# MP-USBA.net
KiCad netlist of a schematic drawn in Altium Designer
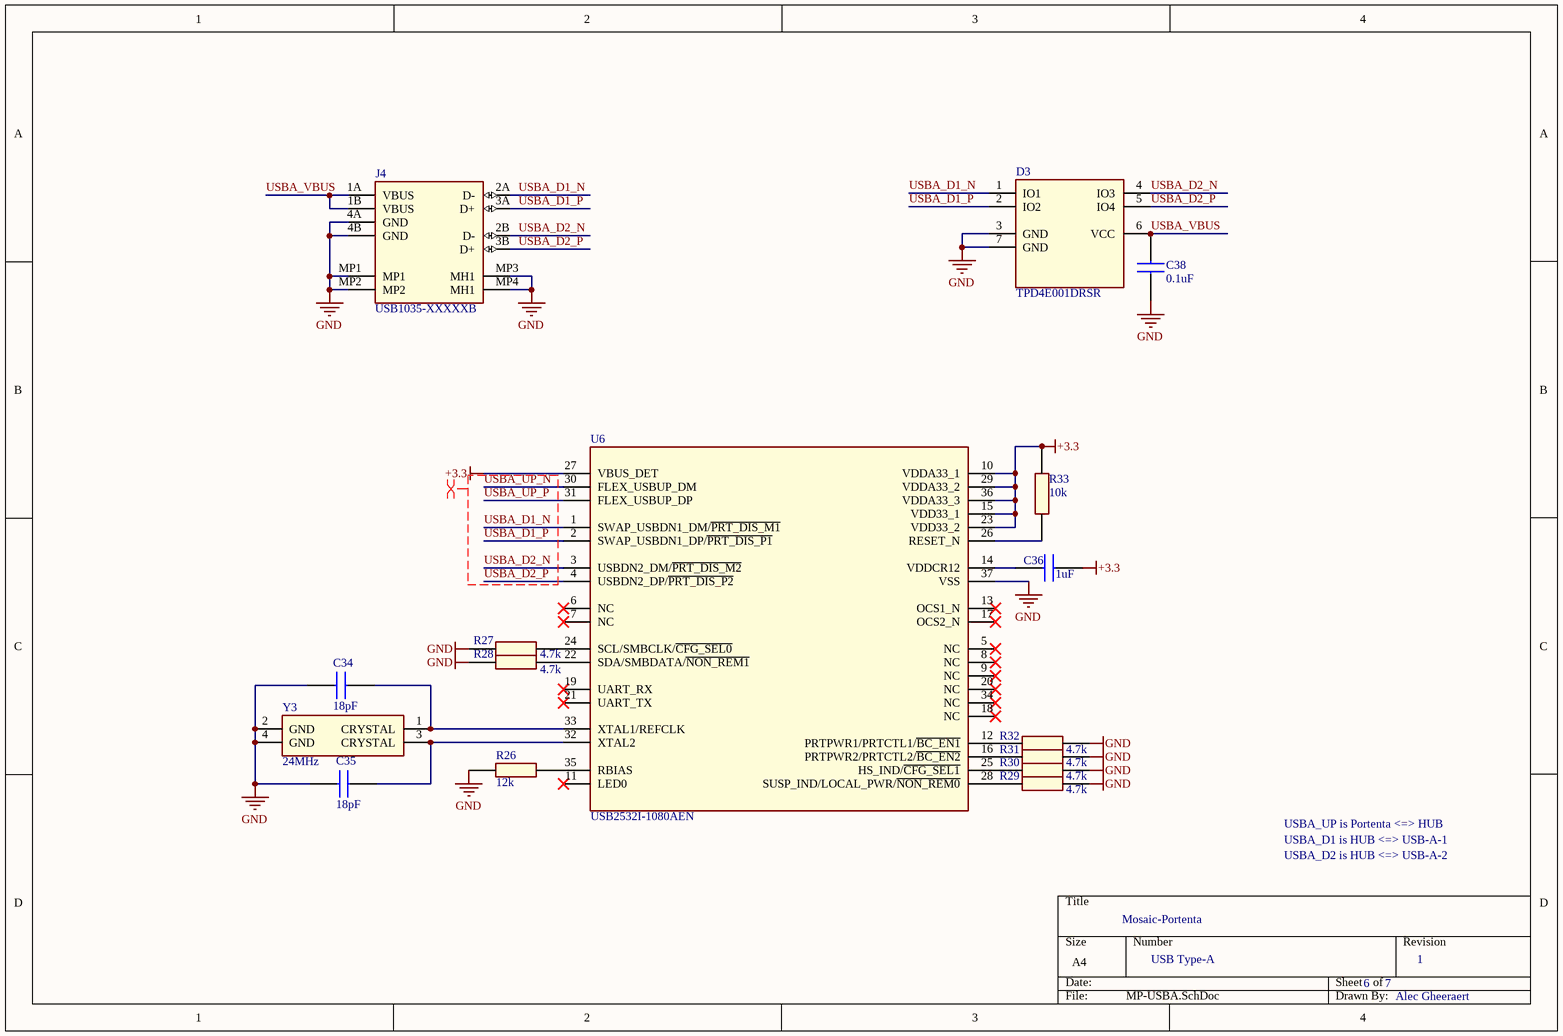
[diagram p0: MP-USBA.SchDoc]

(export (version "E")
  (design (tool "Eeschema 10.0.6"))
  (components
    (comp (ref "C34")
      (value "18pF")
      (footprint "CAPC1608X87N")
      (description "0603 18pF")
      (fields (field (name "TOLERANCE") "5%") (field (name "MANUFACTURER") "Walsin"))
      (libsource (lib "Ghrt") (part "0603N180J160CT"))
    )
    (comp (ref "C35")
      (value "18pF")
      (footprint "CAPC1608X87N")
      (description "0603 18pF")
      (fields (field (name "TOLERANCE") "5%") (field (name "MANUFACTURER") "Walsin"))
      (libsource (lib "Ghrt") (part "0603N180J160CT"))
    )
    (comp (ref "C36")
      (value "1uF")
      (footprint "CAPC1608X100N")
      (description "0603 1µF")
      (fields (field (name "MANUFACTURER") "Walsin") (field (name "TOLERANCE") "10%"))
      (libsource (lib "Ghrt") (part "0603X105K6R3CT"))
    )
    (comp (ref "C38")
      (value "0.1uF")
      (footprint "CAPC1005X55N")
      (description "0402I 0.1µF")
      (fields (field (name "MANUFACTURER") "Walsin") (field (name "TOLERANCE") "10%"))
      (libsource (lib "Ghrt") (part "MG15B104K100CT"))
    )
    (comp (ref "D3")
      (value "TPD4E001DRSR")
      (footprint "SON95P300X300X80-7N-D")
      (description "4-Channel TVS Diodes")
      (libsource (lib "Ghrt") (part "TPD4E001DRSR"))
    )
    (comp (ref "J4")
      (value "USB1035-XXXXXB")
      (footprint "USB1035-XXXXXB")
      (description "USB-2.0 Type A Dual")
      (fields (field (name "MANUFACTURER") "Global Connector Technologies"))
      (libsource (lib "Ghrt") (part "USB1035-XXXXXB"))
    )
    (comp (ref "R26")
      (value "12k")
      (footprint "RESC1005X40N")
      (description "0402I 12k")
      (fields (field (name "TOLERANCE") "1%") (field (name "MANUFACTURER") "Walsin"))
      (libsource (lib "Ghrt") (part "WR04X1202FTL"))
    )
    (comp (ref "R27")
      (value "4.7k")
      (footprint "RESC1005X40N")
      (description "0402I 4.7k")
      (fields (field (name "MANUFACTURER") "Walsin") (field (name "TOLERANCE") "1%"))
      (libsource (lib "Ghrt") (part "WR04X4701FTL"))
    )
    (comp (ref "R28")
      (value "4.7k")
      (footprint "RESC1005X40N")
      (description "0402I 4.7k")
      (fields (field (name "MANUFACTURER") "Walsin") (field (name "TOLERANCE") "1%"))
      (libsource (lib "Ghrt") (part "WR04X4701FTL"))
    )
    (comp (ref "R29")
      (value "4.7k")
      (footprint "RESC1005X40N")
      (description "0402I 4.7k")
      (fields (field (name "MANUFACTURER") "Walsin") (field (name "TOLERANCE") "1%"))
      (libsource (lib "") (part "WR04X4701FTL_1"))
    )
    (comp (ref "R30")
      (value "4.7k")
      (footprint "RESC1005X40N")
      (description "0402I 4.7k")
      (fields (field (name "MANUFACTURER") "Walsin") (field (name "TOLERANCE") "1%"))
      (libsource (lib "") (part "WR04X4701FTL_1"))
    )
    (comp (ref "R31")
      (value "4.7k")
      (footprint "RESC1005X40N")
      (description "0402I 4.7k")
      (fields (field (name "MANUFACTURER") "Walsin") (field (name "TOLERANCE") "1%"))
      (libsource (lib "") (part "WR04X4701FTL_1"))
    )
    (comp (ref "R32")
      (value "4.7k")
      (footprint "RESC1005X40N")
      (description "0402I 4.7k")
      (fields (field (name "MANUFACTURER") "Walsin") (field (name "TOLERANCE") "1%"))
      (libsource (lib "") (part "WR04X4701FTL_1"))
    )
    (comp (ref "R33")
      (value "10k")
      (footprint "RESC1005X40N")
      (description "0402I 10k")
      (fields (field (name "MANUFACTURER") "Walsin") (field (name "TOLERANCE") "1%"))
      (libsource (lib "Ghrt") (part "WR04X1002FTL"))
    )
    (comp (ref "U6")
      (value "USB2532I-1080AEN")
      (footprint "QFN50P600X600X100-37N-D")
      (description "2-Port USB-2.0 Controller Hub")
      (fields (field (name "MANUFACTURER") "Microchip"))
      (libsource (lib "Ghrt") (part "USB2532I-1080AEN"))
    )
    (comp (ref "Y3")
      (value "24MHz")
      (footprint "LFXTAL071257Reel")
      (description "24MHz +/-100ppm Crystal")
      (fields (field (name "TOLERANCE") "10") (field (name "MANUFACTURER") "IQD"))
      (libsource (lib "Ghrt") (part "LFXTAL071257Reel"))
    )
  )
  (nets
    (net (code "1") (name "+3.3") (class "Default")
      (node (ref "C36") (pin "2") (pinfunction "2_2") (pintype "passive"))
      (node (ref "R33") (pin "2") (pinfunction "2_2") (pintype "passive"))
      (node (ref "U6") (pin "10") (pinfunction "VDDA33_1_10") (pintype "passive"))
      (node (ref "U6") (pin "15") (pinfunction "VDD33_1_15") (pintype "passive"))
      (node (ref "U6") (pin "23") (pinfunction "VDD33_2_23") (pintype "passive"))
      (node (ref "U6") (pin "27") (pinfunction "VBUS_DET_27") (pintype "passive"))
      (node (ref "U6") (pin "29") (pinfunction "VDDA33_2_29") (pintype "passive"))
      (node (ref "U6") (pin "36") (pinfunction "VDDA33_3_36") (pintype "passive"))
    )
    (net (code "2") (name "/USBA_D1_N") (class "Default")
      (node (ref "D3") (pin "1") (pinfunction "IO1_1") (pintype "passive"))
      (node (ref "J4") (pin "2A") (pinfunction "D-_2A") (pintype "bidirectional"))
      (node (ref "U6") (pin "1") (pinfunction "SWAP_USBDN1_DM/~{PRT_DIS_M1}_1") (pintype "passive"))
    )
    (net (code "3") (name "/USBA_D1_P") (class "Default")
      (node (ref "D3") (pin "2") (pinfunction "IO2_2") (pintype "passive"))
      (node (ref "J4") (pin "3A") (pinfunction "D+_3A") (pintype "bidirectional"))
      (node (ref "U6") (pin "2") (pinfunction "SWAP_USBDN1_DP/~{PRT_DIS_P1}_2") (pintype "passive"))
    )
    (net (code "4") (name "/USBA_D2_N") (class "Default")
      (node (ref "D3") (pin "4") (pinfunction "IO3_4") (pintype "passive"))
      (node (ref "J4") (pin "2B") (pinfunction "D-_2B") (pintype "bidirectional"))
      (node (ref "U6") (pin "3") (pinfunction "USBDN2_DM/~{PRT_DIS_M2}_3") (pintype "passive"))
    )
    (net (code "5") (name "/USBA_D2_P") (class "Default")
      (node (ref "D3") (pin "5") (pinfunction "IO4_5") (pintype "passive"))
      (node (ref "J4") (pin "3B") (pinfunction "D+_3B") (pintype "bidirectional"))
      (node (ref "U6") (pin "4") (pinfunction "USBDN2_DP/~{PRT_DIS_P2}_4") (pintype "passive"))
    )
    (net (code "6") (name "/USBA_UP_N") (class "Default")
      (node (ref "U6") (pin "30") (pinfunction "FLEX_USBUP_DM_30") (pintype "passive"))
    )
    (net (code "7") (name "/USBA_UP_P") (class "Default")
      (node (ref "U6") (pin "31") (pinfunction "FLEX_USBUP_DP_31") (pintype "passive"))
    )
    (net (code "8") (name "/USBA_VBUS") (class "Default")
      (node (ref "C38") (pin "1") (pinfunction "1_1") (pintype "passive"))
      (node (ref "D3") (pin "6") (pinfunction "VCC_6") (pintype "passive"))
      (node (ref "J4") (pin "1A") (pinfunction "VBUS_1A") (pintype "power_in"))
      (node (ref "J4") (pin "1B") (pinfunction "VBUS_1B") (pintype "power_in"))
    )
    (net (code "9") (name "GND") (class "Default")
      (node (ref "C34") (pin "2") (pinfunction "2_2") (pintype "passive"))
      (node (ref "C35") (pin "2") (pinfunction "2_2") (pintype "passive"))
      (node (ref "C38") (pin "2") (pinfunction "2_2") (pintype "passive"))
      (node (ref "D3") (pin "3") (pinfunction "GND_3") (pintype "passive"))
      (node (ref "D3") (pin "7") (pinfunction "GND_7") (pintype "passive"))
      (node (ref "J4") (pin "4A") (pinfunction "GND_4A") (pintype "power_in"))
      (node (ref "J4") (pin "4B") (pinfunction "GND_4B") (pintype "power_in"))
      (node (ref "J4") (pin "MP1") (pinfunction "MP1_MP1") (pintype "passive"))
      (node (ref "J4") (pin "MP2") (pinfunction "MP2_MP2") (pintype "passive"))
      (node (ref "J4") (pin "MP3") (pinfunction "MH1_MP3") (pintype "passive"))
      (node (ref "J4") (pin "MP4") (pinfunction "MH1_MP4") (pintype "passive"))
      (node (ref "R26") (pin "2") (pinfunction "2_2") (pintype "passive"))
      (node (ref "R27") (pin "2") (pinfunction "2_2") (pintype "passive"))
      (node (ref "R28") (pin "2") (pinfunction "2_2") (pintype "passive"))
      (node (ref "R29") (pin "2") (pinfunction "2_2") (pintype "passive"))
      (node (ref "R30") (pin "2") (pinfunction "2_2") (pintype "passive"))
      (node (ref "R31") (pin "2") (pinfunction "2_2") (pintype "passive"))
      (node (ref "R32") (pin "2") (pinfunction "2_2") (pintype "passive"))
      (node (ref "U6") (pin "37") (pinfunction "VSS_37") (pintype "passive"))
      (node (ref "Y3") (pin "2") (pinfunction "GND_2") (pintype "passive"))
      (node (ref "Y3") (pin "4") (pinfunction "GND_4") (pintype "passive"))
    )
    (net (code "10") (name "Net-(U6-HS_IND{slash}~{CFG_SEL1})") (class "Default")
      (node (ref "R30") (pin "1") (pinfunction "1_1") (pintype "passive"))
      (node (ref "U6") (pin "25") (pinfunction "HS_IND/~{CFG_SEL1}_25") (pintype "passive"))
    )
    (net (code "11") (name "Net-(U6-PRTPWR1{slash}PRTCTL1{slash}~{BC_EN1})") (class "Default")
      (node (ref "R32") (pin "1") (pinfunction "1_1") (pintype "passive"))
      (node (ref "U6") (pin "12") (pinfunction "PRTPWR1/PRTCTL1/~{BC_EN1}_12") (pintype "passive"))
    )
    (net (code "12") (name "Net-(U6-PRTPWR2{slash}PRTCTL2{slash}~{BC_EN2})") (class "Default")
      (node (ref "R31") (pin "1") (pinfunction "1_1") (pintype "passive"))
      (node (ref "U6") (pin "16") (pinfunction "PRTPWR2/PRTCTL2/~{BC_EN2}_16") (pintype "passive"))
    )
    (net (code "13") (name "Net-(U6-RBIAS)") (class "Default")
      (node (ref "R26") (pin "1") (pinfunction "1_1") (pintype "passive"))
      (node (ref "U6") (pin "35") (pinfunction "RBIAS_35") (pintype "passive"))
    )
    (net (code "14") (name "Net-(U6-RESET_N)") (class "Default")
      (node (ref "R33") (pin "1") (pinfunction "1_1") (pintype "passive"))
      (node (ref "U6") (pin "26") (pinfunction "RESET_N_26") (pintype "passive"))
    )
    (net (code "15") (name "Net-(U6-SCL{slash}SMBCLK{slash}~{CFG_SEL0})") (class "Default")
      (node (ref "R27") (pin "1") (pinfunction "1_1") (pintype "passive"))
      (node (ref "U6") (pin "24") (pinfunction "SCL/SMBCLK/~{CFG_SEL0}_24") (pintype "passive"))
    )
    (net (code "16") (name "Net-(U6-SDA{slash}SMBDATA{slash}~{NON_REM1})") (class "Default")
      (node (ref "R28") (pin "1") (pinfunction "1_1") (pintype "passive"))
      (node (ref "U6") (pin "22") (pinfunction "SDA/SMBDATA/~{NON_REM1}_22") (pintype "passive"))
    )
    (net (code "17") (name "Net-(U6-SUSP_IND{slash}LOCAL_PWR{slash}~{NON_REM0})") (class "Default")
      (node (ref "R29") (pin "1") (pinfunction "1_1") (pintype "passive"))
      (node (ref "U6") (pin "28") (pinfunction "SUSP_IND/LOCAL_PWR/~{NON_REM0}_28") (pintype "passive"))
    )
    (net (code "18") (name "Net-(U6-VDDCR12)") (class "Default")
      (node (ref "C36") (pin "1") (pinfunction "1_1") (pintype "passive"))
      (node (ref "U6") (pin "14") (pinfunction "VDDCR12_14") (pintype "passive"))
    )
    (net (code "19") (name "Net-(U6-XTAL1{slash}REFCLK)") (class "Default")
      (node (ref "C34") (pin "1") (pinfunction "1_1") (pintype "passive"))
      (node (ref "U6") (pin "33") (pinfunction "XTAL1/REFCLK_33") (pintype "passive"))
      (node (ref "Y3") (pin "1") (pinfunction "CRYSTAL_1") (pintype "passive"))
    )
    (net (code "20") (name "Net-(U6-XTAL2)") (class "Default")
      (node (ref "C35") (pin "1") (pinfunction "1_1") (pintype "passive"))
      (node (ref "U6") (pin "32") (pinfunction "XTAL2_32") (pintype "passive"))
      (node (ref "Y3") (pin "3") (pinfunction "CRYSTAL_3") (pintype "passive"))
    )
    (net (code "21") (name "unconnected-(U6-LED0-Pad11)") (class "Default")
      (node (ref "U6") (pin "11") (pinfunction "LED0_11") (pintype "passive+no_connect"))
    )
    (net (code "22") (name "unconnected-(U6-NC-Pad5)") (class "Default")
      (node (ref "U6") (pin "5") (pinfunction "NC_5") (pintype "passive+no_connect"))
    )
    (net (code "23") (name "unconnected-(U6-NC-Pad6)") (class "Default")
      (node (ref "U6") (pin "6") (pinfunction "NC_6") (pintype "passive+no_connect"))
    )
    (net (code "24") (name "unconnected-(U6-NC-Pad7)") (class "Default")
      (node (ref "U6") (pin "7") (pinfunction "NC_7") (pintype "passive+no_connect"))
    )
    (net (code "25") (name "unconnected-(U6-NC-Pad8)") (class "Default")
      (node (ref "U6") (pin "8") (pinfunction "NC_8") (pintype "passive+no_connect"))
    )
    (net (code "26") (name "unconnected-(U6-NC-Pad9)") (class "Default")
      (node (ref "U6") (pin "9") (pinfunction "NC_9") (pintype "passive+no_connect"))
    )
    (net (code "27") (name "unconnected-(U6-NC-Pad18)") (class "Default")
      (node (ref "U6") (pin "18") (pinfunction "NC_18") (pintype "passive+no_connect"))
    )
    (net (code "28") (name "unconnected-(U6-NC-Pad20)") (class "Default")
      (node (ref "U6") (pin "20") (pinfunction "NC_20") (pintype "passive+no_connect"))
    )
    (net (code "29") (name "unconnected-(U6-NC-Pad34)") (class "Default")
      (node (ref "U6") (pin "34") (pinfunction "NC_34") (pintype "passive+no_connect"))
    )
    (net (code "30") (name "unconnected-(U6-OCS1_N-Pad13)") (class "Default")
      (node (ref "U6") (pin "13") (pinfunction "OCS1_N_13") (pintype "passive+no_connect"))
    )
    (net (code "31") (name "unconnected-(U6-OCS2_N-Pad17)") (class "Default")
      (node (ref "U6") (pin "17") (pinfunction "OCS2_N_17") (pintype "passive+no_connect"))
    )
    (net (code "32") (name "unconnected-(U6-UART_RX-Pad19)") (class "Default")
      (node (ref "U6") (pin "19") (pinfunction "UART_RX_19") (pintype "passive+no_connect"))
    )
    (net (code "33") (name "unconnected-(U6-UART_TX-Pad21)") (class "Default")
      (node (ref "U6") (pin "21") (pinfunction "UART_TX_21") (pintype "passive+no_connect"))
    )
  )
)
